# TempBar_V1.net
KiCad netlist of a schematic drawn in EAGLE
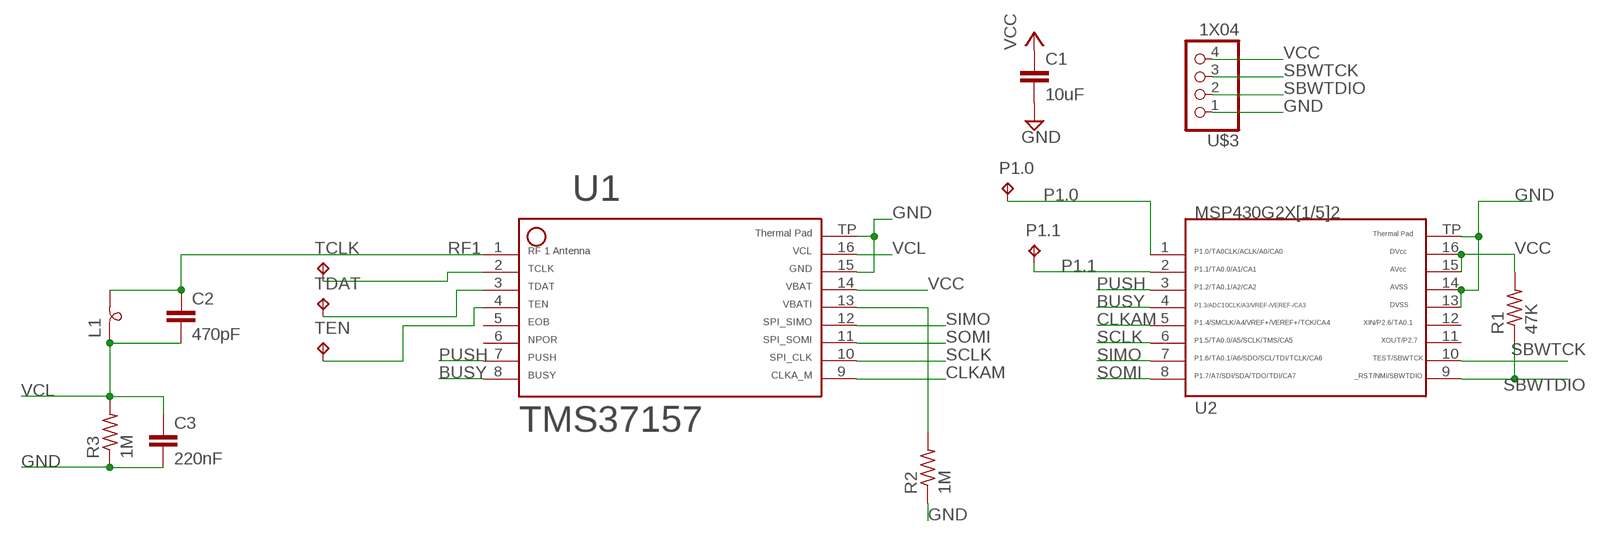
[diagram p0: schematic, sheet 1]

(export (version "E")
  (design (tool "Eeschema 10.0.6"))
  (components
    (comp (ref "C1")
      (value "10uF")
      (footprint "eagle-import:C0603")
      (libsource (lib "eagle-import") (part "C-EUC0603"))
    )
    (comp (ref "C2")
      (value "470pF")
      (footprint "eagle-import:C0402")
      (libsource (lib "eagle-import") (part "C-EUC0402"))
    )
    (comp (ref "C3")
      (value "220nF")
      (footprint "eagle-import:C0402")
      (libsource (lib "eagle-import") (part "C-EUC0402"))
    )
    (comp (ref "L1")
      (value "SM-B5")
      (footprint "eagle-import:SM-B5")
      (libsource (lib "eagle-import") (part "SM-B5"))
    )
    (comp (ref "P1.0")
      (value "TPTP08R")
      (footprint "eagle-import:TP08R")
      (libsource (lib "eagle-import") (part "TPTP08R"))
    )
    (comp (ref "P1.1")
      (value "TPTP08R")
      (footprint "eagle-import:TP08R")
      (libsource (lib "eagle-import") (part "TPTP08R"))
    )
    (comp (ref "R1")
      (value "47K")
      (footprint "eagle-import:R0402")
      (libsource (lib "eagle-import") (part "R-US_R0402"))
    )
    (comp (ref "R2")
      (value "1M")
      (footprint "eagle-import:R0402")
      (libsource (lib "eagle-import") (part "R-US_R0402"))
    )
    (comp (ref "R3")
      (value "1M")
      (footprint "eagle-import:R0402")
      (libsource (lib "eagle-import") (part "R-US_R0402"))
    )
    (comp (ref "TCLK")
      (value "TPTP08R")
      (footprint "eagle-import:TP08R")
      (libsource (lib "eagle-import") (part "TPTP08R"))
    )
    (comp (ref "TDAT")
      (value "TPTP08R")
      (footprint "eagle-import:TP08R")
      (libsource (lib "eagle-import") (part "TPTP08R"))
    )
    (comp (ref "TEN")
      (value "TPTP08R")
      (footprint "eagle-import:TP08R")
      (libsource (lib "eagle-import") (part "TPTP08R"))
    )
    (comp (ref "U$3")
      (value "1X04")
      (footprint "eagle-import:1X06")
      (libsource (lib "eagle-import") (part "1X04"))
    )
    (comp (ref "U1")
      (value "TMS37157")
      (footprint "eagle-import:RSA16")
      (libsource (lib "eagle-import") (part "TMS37157"))
    )
    (comp (ref "U2")
      (value "G2X[1/5]2---RSA16")
      (footprint "eagle-import:RSA16")
      (libsource (lib "eagle-import") (part "G2X[1/5]2---RSA16"))
    )
  )
  (nets
    (net (code "1") (name "/BUSY") (class "Default")
      (node (ref "U1") (pin "8") (pinfunction "8_8") (pintype "bidirectional"))
      (node (ref "U2") (pin "4") (pinfunction "4_4") (pintype "bidirectional"))
    )
    (net (code "2") (name "/CLKAM") (class "Default")
      (node (ref "U1") (pin "9") (pinfunction "9_9") (pintype "bidirectional"))
      (node (ref "U2") (pin "5") (pinfunction "5_5") (pintype "bidirectional"))
    )
    (net (code "3") (name "/P1.0") (class "Default")
      (node (ref "P1.0") (pin "TP") (pinfunction "TP_TP") (pintype "input"))
      (node (ref "U2") (pin "1") (pinfunction "1_1") (pintype "bidirectional"))
    )
    (net (code "4") (name "/P1.1") (class "Default")
      (node (ref "P1.1") (pin "TP") (pinfunction "TP_TP") (pintype "input"))
      (node (ref "U2") (pin "2") (pinfunction "2_2") (pintype "bidirectional"))
    )
    (net (code "5") (name "/PUSH") (class "Default")
      (node (ref "U1") (pin "7") (pinfunction "7_7") (pintype "bidirectional"))
      (node (ref "U2") (pin "3") (pinfunction "3_3") (pintype "bidirectional"))
    )
    (net (code "6") (name "/RF1") (class "Default")
      (node (ref "C2") (pin "1") (pinfunction "1_1") (pintype "passive"))
      (node (ref "L1") (pin "2") (pinfunction "2_2") (pintype "passive"))
      (node (ref "U1") (pin "1") (pinfunction "1_1") (pintype "bidirectional"))
    )
    (net (code "7") (name "/SBWTCK") (class "Default")
      (node (ref "U$3") (pin "3") (pinfunction "3_3") (pintype "passive"))
      (node (ref "U2") (pin "10") (pinfunction "10_10") (pintype "bidirectional"))
    )
    (net (code "8") (name "/SBWTDIO") (class "Default")
      (node (ref "R1") (pin "1") (pinfunction "1_1") (pintype "passive"))
      (node (ref "U$3") (pin "2") (pinfunction "2_2") (pintype "passive"))
      (node (ref "U2") (pin "9") (pinfunction "9_9") (pintype "bidirectional"))
    )
    (net (code "9") (name "/SCLK") (class "Default")
      (node (ref "U1") (pin "10") (pinfunction "10_10") (pintype "input"))
      (node (ref "U2") (pin "6") (pinfunction "6_6") (pintype "bidirectional"))
    )
    (net (code "10") (name "/SIMO") (class "Default")
      (node (ref "U1") (pin "12") (pinfunction "12_12") (pintype "bidirectional"))
      (node (ref "U2") (pin "7") (pinfunction "7_7") (pintype "bidirectional"))
    )
    (net (code "11") (name "/SOMI") (class "Default")
      (node (ref "U1") (pin "11") (pinfunction "11_11") (pintype "bidirectional"))
      (node (ref "U2") (pin "8") (pinfunction "8_8") (pintype "bidirectional"))
    )
    (net (code "12") (name "/VCL") (class "Default")
      (node (ref "C2") (pin "2") (pinfunction "2_2") (pintype "passive"))
      (node (ref "C3") (pin "1") (pinfunction "1_1") (pintype "passive"))
      (node (ref "L1") (pin "1") (pinfunction "1_1") (pintype "passive"))
      (node (ref "R3") (pin "2") (pinfunction "2_2") (pintype "passive"))
      (node (ref "U1") (pin "16") (pinfunction "16_16") (pintype "power_in"))
    )
    (net (code "13") (name "GND") (class "Default")
      (node (ref "C1") (pin "2") (pinfunction "2_2") (pintype "passive"))
      (node (ref "C3") (pin "2") (pinfunction "2_2") (pintype "passive"))
      (node (ref "R2") (pin "1") (pinfunction "1_1") (pintype "passive"))
      (node (ref "R3") (pin "1") (pinfunction "1_1") (pintype "passive"))
      (node (ref "U$3") (pin "1") (pinfunction "1_1") (pintype "passive"))
      (node (ref "U1") (pin "15") (pinfunction "15_15") (pintype "power_in"))
      (node (ref "U1") (pin "TP") (pinfunction "PP_TP") (pintype "power_in"))
      (node (ref "U2") (pin "13") (pinfunction "13_13") (pintype "bidirectional"))
      (node (ref "U2") (pin "14") (pinfunction "14_14") (pintype "bidirectional"))
      (node (ref "U2") (pin "TP") (pinfunction "TP_TP") (pintype "bidirectional"))
    )
    (net (code "14") (name "Net-(R2-Pad2)") (class "Default")
      (node (ref "R2") (pin "2") (pinfunction "2_2") (pintype "passive"))
      (node (ref "U1") (pin "13") (pinfunction "13_13") (pintype "power_in"))
    )
    (net (code "15") (name "Net-(TCLK-PadTP)") (class "Default")
      (node (ref "TCLK") (pin "TP") (pinfunction "TP_TP") (pintype "input"))
      (node (ref "U1") (pin "2") (pinfunction "2_2") (pintype "bidirectional"))
    )
    (net (code "16") (name "Net-(TDAT-PadTP)") (class "Default")
      (node (ref "TDAT") (pin "TP") (pinfunction "TP_TP") (pintype "input"))
      (node (ref "U1") (pin "3") (pinfunction "3_3") (pintype "bidirectional"))
    )
    (net (code "17") (name "Net-(TEN-PadTP)") (class "Default")
      (node (ref "TEN") (pin "TP") (pinfunction "TP_TP") (pintype "input"))
      (node (ref "U1") (pin "4") (pinfunction "4_4") (pintype "bidirectional"))
    )
    (net (code "18") (name "VCC") (class "Default")
      (node (ref "C1") (pin "1") (pinfunction "1_1") (pintype "passive"))
      (node (ref "R1") (pin "2") (pinfunction "2_2") (pintype "passive"))
      (node (ref "U$3") (pin "4") (pinfunction "4_4") (pintype "passive"))
      (node (ref "U1") (pin "14") (pinfunction "14_14") (pintype "power_in"))
      (node (ref "U2") (pin "15") (pinfunction "15_15") (pintype "bidirectional"))
      (node (ref "U2") (pin "16") (pinfunction "16_16") (pintype "bidirectional"))
    )
    (net (code "19") (name "unconnected-(U1-Pad5)") (class "Default")
      (node (ref "U1") (pin "5") (pinfunction "5_5") (pintype "bidirectional"))
    )
    (net (code "20") (name "unconnected-(U1-Pad6)") (class "Default")
      (node (ref "U1") (pin "6") (pinfunction "6_6") (pintype "bidirectional"))
    )
    (net (code "21") (name "unconnected-(U2-Pad11)") (class "Default")
      (node (ref "U2") (pin "11") (pinfunction "11_11") (pintype "bidirectional"))
    )
    (net (code "22") (name "unconnected-(U2-Pad12)") (class "Default")
      (node (ref "U2") (pin "12") (pinfunction "12_12") (pintype "bidirectional"))
    )
  )
)
